# RJ45-1.net
KiCad netlist of a schematic drawn in Altium Designer
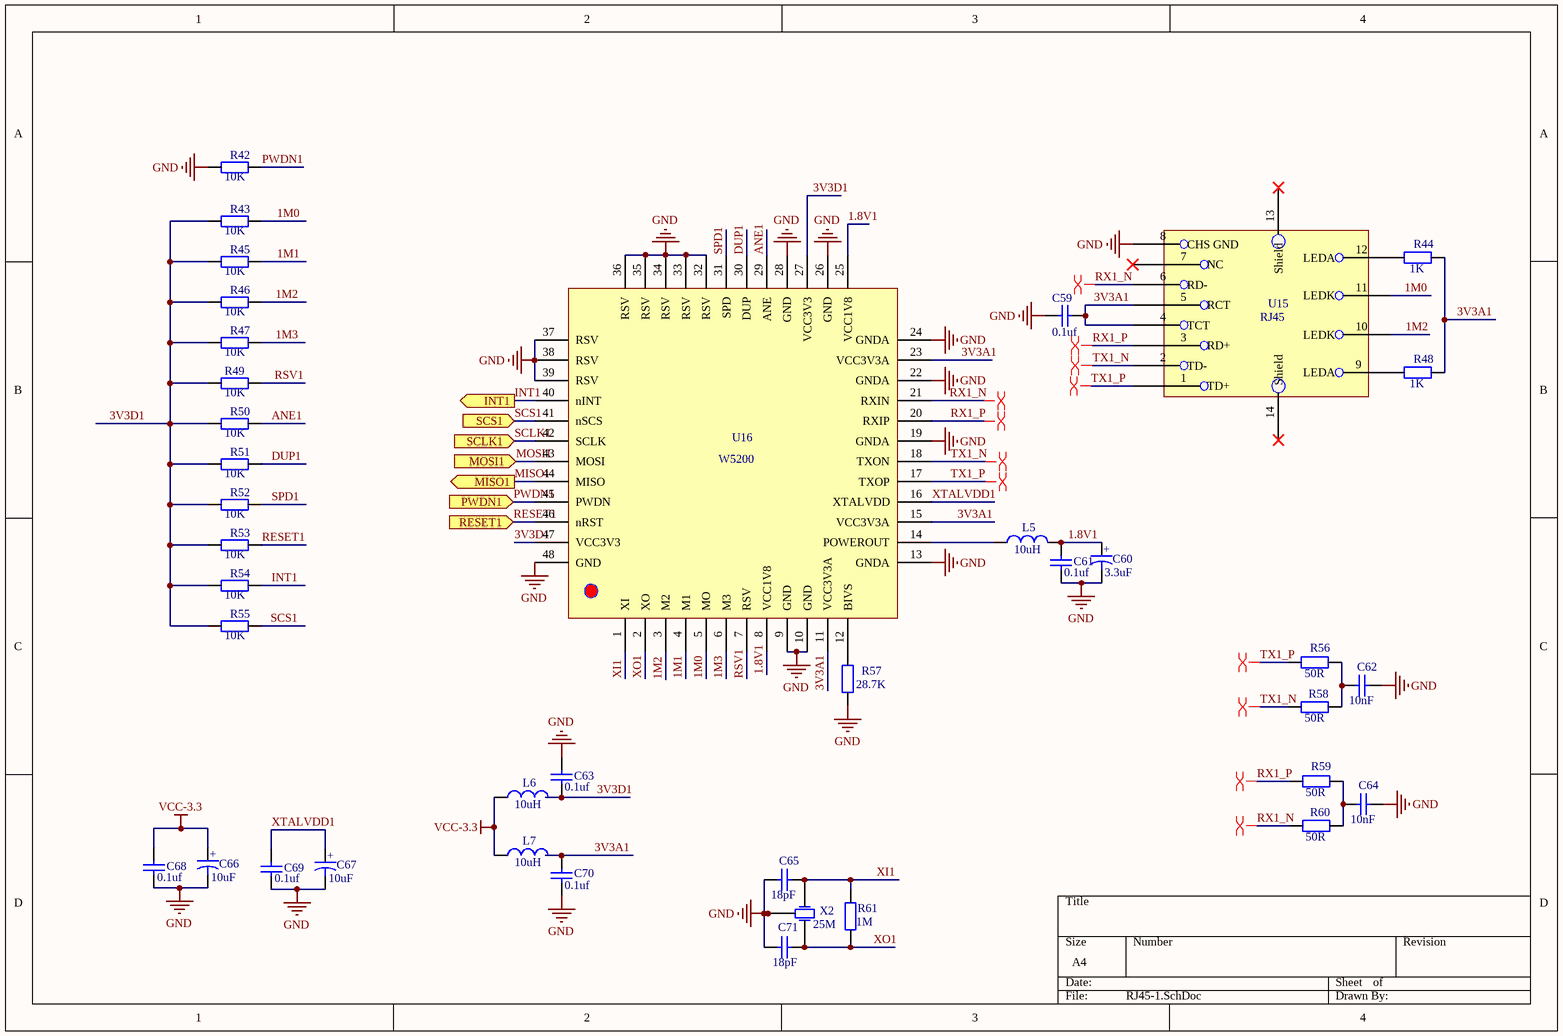
[diagram p0: RJ45-1.SchDoc]

(export (version "E")
  (design (tool "Eeschema 10.0.6"))
  (components
    (comp (ref "C59")
      (value "0.1uf")
      (footprint "0603")
      (fields (field (name "Comment") "Capacitor-0603"))
      (libsource (lib "原理图库") (part "Capacitor-0603"))
    )
    (comp (ref "C60")
      (value "3.3uF")
      (footprint "钽电容1206（A3216）")
      (fields (field (name "ALTIUM_UNNAMED_1") "+") (field (name "Comment") "电解电容"))
      (libsource (lib "原理图库") (part "电解电容"))
    )
    (comp (ref "C61")
      (value "0.1uf")
      (footprint "0603")
      (fields (field (name "Comment") "Capacitor-0603"))
      (libsource (lib "原理图库") (part "Capacitor-0603"))
    )
    (comp (ref "C62")
      (value "10nF")
      (footprint "0603")
      (fields (field (name "Comment") "Capacitor-0603"))
      (libsource (lib "原理图库") (part "Capacitor-0603"))
    )
    (comp (ref "C63")
      (value "0.1uf")
      (footprint "0603")
      (fields (field (name "Comment") "Capacitor-0603"))
      (libsource (lib "原理图库") (part "Capacitor-0603"))
    )
    (comp (ref "C64")
      (value "10nF")
      (footprint "0603")
      (fields (field (name "Comment") "Capacitor-0603"))
      (libsource (lib "原理图库") (part "Capacitor-0603"))
    )
    (comp (ref "C65")
      (value "18pF")
      (footprint "0603")
      (fields (field (name "Comment") "Capacitor-0603"))
      (libsource (lib "原理图库") (part "Capacitor-0603"))
    )
    (comp (ref "C66")
      (value "10uF")
      (footprint "钽电容1206（A3216）")
      (fields (field (name "ALTIUM_UNNAMED_1") "+") (field (name "Comment") "电解电容"))
      (libsource (lib "原理图库") (part "电解电容"))
    )
    (comp (ref "C67")
      (value "10uF")
      (footprint "钽电容1206（A3216）")
      (fields (field (name "ALTIUM_UNNAMED_1") "+") (field (name "Comment") "电解电容"))
      (libsource (lib "原理图库") (part "电解电容"))
    )
    (comp (ref "C68")
      (value "0.1uf")
      (footprint "0603")
      (fields (field (name "Comment") "Capacitor-0603"))
      (libsource (lib "原理图库") (part "Capacitor-0603"))
    )
    (comp (ref "C69")
      (value "0.1uf")
      (footprint "0603")
      (fields (field (name "Comment") "Capacitor-0603"))
      (libsource (lib "原理图库") (part "Capacitor-0603"))
    )
    (comp (ref "C70")
      (value "0.1uf")
      (footprint "0603")
      (fields (field (name "Comment") "Capacitor-0603"))
      (libsource (lib "原理图库") (part "Capacitor-0603"))
    )
    (comp (ref "C71")
      (value "18pF")
      (footprint "0603")
      (fields (field (name "Comment") "Capacitor-0603"))
      (libsource (lib "原理图库") (part "Capacitor-0603"))
    )
    (comp (ref "L5")
      (value "10uH")
      (footprint "0805")
      (fields (field (name "Comment") "Inductor"))
      (libsource (lib "原理图库") (part "Inductor"))
    )
    (comp (ref "L6")
      (value "10uH")
      (footprint "0805")
      (fields (field (name "Comment") "Inductor"))
      (libsource (lib "原理图库") (part "Inductor"))
    )
    (comp (ref "L7")
      (value "10uH")
      (footprint "0805")
      (fields (field (name "Comment") "Inductor"))
      (libsource (lib "原理图库") (part "Inductor"))
    )
    (comp (ref "R42")
      (value "10K")
      (footprint "0603")
      (fields (field (name "Comment") "Resistor-0603"))
      (libsource (lib "原理图库") (part "Resistor-0603"))
    )
    (comp (ref "R43")
      (value "10K")
      (footprint "0603")
      (fields (field (name "Comment") "Resistor-0603"))
      (libsource (lib "原理图库") (part "Resistor-0603"))
    )
    (comp (ref "R44")
      (value "1K")
      (footprint "0603")
      (fields (field (name "Comment") "Resistor-0603"))
      (libsource (lib "原理图库") (part "Resistor-0603"))
    )
    (comp (ref "R45")
      (value "10K")
      (footprint "0603")
      (fields (field (name "Comment") "Resistor-0603"))
      (libsource (lib "原理图库") (part "Resistor-0603"))
    )
    (comp (ref "R46")
      (value "10K")
      (footprint "0603")
      (fields (field (name "Comment") "Resistor-0603"))
      (libsource (lib "原理图库") (part "Resistor-0603"))
    )
    (comp (ref "R47")
      (value "10K")
      (footprint "0603")
      (fields (field (name "Comment") "Resistor-0603"))
      (libsource (lib "原理图库") (part "Resistor-0603"))
    )
    (comp (ref "R48")
      (value "1K")
      (footprint "0603")
      (fields (field (name "Comment") "Resistor-0603"))
      (libsource (lib "原理图库") (part "Resistor-0603"))
    )
    (comp (ref "R49")
      (value "10K")
      (footprint "0603")
      (fields (field (name "Comment") "Resistor-0603"))
      (libsource (lib "原理图库") (part "Resistor-0603"))
    )
    (comp (ref "R50")
      (value "10K")
      (footprint "0603")
      (fields (field (name "Comment") "Resistor-0603"))
      (libsource (lib "原理图库") (part "Resistor-0603"))
    )
    (comp (ref "R51")
      (value "10K")
      (footprint "0603")
      (fields (field (name "Comment") "Resistor-0603"))
      (libsource (lib "原理图库") (part "Resistor-0603"))
    )
    (comp (ref "R52")
      (value "10K")
      (footprint "0603")
      (fields (field (name "Comment") "Resistor-0603"))
      (libsource (lib "原理图库") (part "Resistor-0603"))
    )
    (comp (ref "R53")
      (value "10K")
      (footprint "0603")
      (fields (field (name "Comment") "Resistor-0603"))
      (libsource (lib "原理图库") (part "Resistor-0603"))
    )
    (comp (ref "R54")
      (value "10K")
      (footprint "0603")
      (fields (field (name "Comment") "Resistor-0603"))
      (libsource (lib "原理图库") (part "Resistor-0603"))
    )
    (comp (ref "R55")
      (value "10K")
      (footprint "0603")
      (fields (field (name "Comment") "Resistor-0603"))
      (libsource (lib "原理图库") (part "Resistor-0603"))
    )
    (comp (ref "R56")
      (value "50R")
      (footprint "0603")
      (fields (field (name "Comment") "Resistor-0603"))
      (libsource (lib "原理图库") (part "Resistor-0603"))
    )
    (comp (ref "R57")
      (value "28.7K")
      (footprint "0603")
      (fields (field (name "Comment") "Resistor-0603"))
      (libsource (lib "") (part "Resistor-0603_1"))
    )
    (comp (ref "R58")
      (value "50R")
      (footprint "0603")
      (fields (field (name "Comment") "Resistor-0603"))
      (libsource (lib "原理图库") (part "Resistor-0603"))
    )
    (comp (ref "R59")
      (value "50R")
      (footprint "0603")
      (fields (field (name "Comment") "Resistor-0603"))
      (libsource (lib "原理图库") (part "Resistor-0603"))
    )
    (comp (ref "R60")
      (value "50R")
      (footprint "0603")
      (fields (field (name "Comment") "Resistor-0603"))
      (libsource (lib "原理图库") (part "Resistor-0603"))
    )
    (comp (ref "R61")
      (value "1M")
      (footprint "0603")
      (fields (field (name "Comment") "Resistor-0603"))
      (libsource (lib "") (part "Resistor-0603_2"))
    )
    (comp (ref "U15")
      (value "RJ45")
      (footprint "RJ45")
      (fields (field (name "NAME") "RJ45"))
      (libsource (lib "原理图库") (part "RJ45"))
    )
    (comp (ref "U16")
      (value "W5200-Chip")
      (footprint "W5200-Chip")
      (fields (field (name "NAME") "W5200"))
      (libsource (lib "原理图库") (part "W5200-Chip"))
    )
    (comp (ref "X2")
      (value "25M")
      (footprint "3225无源晶振")
      (fields (field (name "Comment") "3225无源晶振"))
      (libsource (lib "原理图库") (part "3225无源晶振"))
    )
  )
  (nets
    (net (code "1") (name "/1.8V1") (class "Default")
      (node (ref "C60") (pin "2") (pinfunction "2_2") (pintype "passive"))
      (node (ref "C61") (pin "2") (pinfunction "2_2") (pintype "passive"))
      (node (ref "L5") (pin "2") (pinfunction "2_2") (pintype "passive"))
      (node (ref "U16") (pin "25") (pinfunction "VCC1V8_25") (pintype "passive"))
      (node (ref "U16") (pin "8") (pinfunction "VCC1V8_8") (pintype "passive"))
    )
    (net (code "2") (name "/1M0") (class "Default")
      (node (ref "R43") (pin "2") (pinfunction "2_2") (pintype "passive"))
      (node (ref "U15") (pin "11") (pinfunction "LEDK_11") (pintype "passive"))
      (node (ref "U16") (pin "5") (pinfunction "MO_5") (pintype "passive"))
    )
    (net (code "3") (name "/1M1") (class "Default")
      (node (ref "R45") (pin "2") (pinfunction "2_2") (pintype "passive"))
      (node (ref "U16") (pin "4") (pinfunction "M1_4") (pintype "passive"))
    )
    (net (code "4") (name "/1M2") (class "Default")
      (node (ref "R46") (pin "2") (pinfunction "2_2") (pintype "passive"))
      (node (ref "U15") (pin "10") (pinfunction "LEDK_10") (pintype "passive"))
      (node (ref "U16") (pin "3") (pinfunction "M2_3") (pintype "passive"))
    )
    (net (code "5") (name "/1M3") (class "Default")
      (node (ref "R47") (pin "2") (pinfunction "2_2") (pintype "passive"))
      (node (ref "U16") (pin "6") (pinfunction "M3_6") (pintype "passive"))
    )
    (net (code "6") (name "/3V3A1") (class "Default")
      (node (ref "C59") (pin "1") (pinfunction "1_1") (pintype "passive"))
      (node (ref "C70") (pin "1") (pinfunction "1_1") (pintype "passive"))
      (node (ref "L7") (pin "2") (pinfunction "2_2") (pintype "passive"))
      (node (ref "R44") (pin "2") (pinfunction "2_2") (pintype "passive"))
      (node (ref "R48") (pin "2") (pinfunction "2_2") (pintype "passive"))
      (node (ref "U15") (pin "4") (pinfunction "TCT_4") (pintype "passive"))
      (node (ref "U15") (pin "5") (pinfunction "RCT_5") (pintype "passive"))
      (node (ref "U16") (pin "11") (pinfunction "VCC3V3A_11") (pintype "passive"))
      (node (ref "U16") (pin "15") (pinfunction "VCC3V3A_15") (pintype "passive"))
      (node (ref "U16") (pin "23") (pinfunction "VCC3V3A_23") (pintype "passive"))
    )
    (net (code "7") (name "/3V3D1") (class "Default")
      (node (ref "C63") (pin "1") (pinfunction "1_1") (pintype "passive"))
      (node (ref "L6") (pin "2") (pinfunction "2_2") (pintype "passive"))
      (node (ref "R43") (pin "1") (pinfunction "1_1") (pintype "passive"))
      (node (ref "R45") (pin "1") (pinfunction "1_1") (pintype "passive"))
      (node (ref "R46") (pin "1") (pinfunction "1_1") (pintype "passive"))
      (node (ref "R47") (pin "1") (pinfunction "1_1") (pintype "passive"))
      (node (ref "R49") (pin "1") (pinfunction "1_1") (pintype "passive"))
      (node (ref "R50") (pin "1") (pinfunction "1_1") (pintype "passive"))
      (node (ref "R51") (pin "1") (pinfunction "1_1") (pintype "passive"))
      (node (ref "R52") (pin "1") (pinfunction "1_1") (pintype "passive"))
      (node (ref "R53") (pin "1") (pinfunction "1_1") (pintype "passive"))
      (node (ref "R54") (pin "1") (pinfunction "1_1") (pintype "passive"))
      (node (ref "R55") (pin "1") (pinfunction "1_1") (pintype "passive"))
      (node (ref "U16") (pin "27") (pinfunction "VCC3V3_27") (pintype "passive"))
      (node (ref "U16") (pin "47") (pinfunction "VCC3V3_47") (pintype "passive"))
    )
    (net (code "8") (name "/ANE1") (class "Default")
      (node (ref "R50") (pin "2") (pinfunction "2_2") (pintype "passive"))
      (node (ref "U16") (pin "29") (pinfunction "ANE_29") (pintype "passive"))
    )
    (net (code "9") (name "/DUP1") (class "Default")
      (node (ref "R51") (pin "2") (pinfunction "2_2") (pintype "passive"))
      (node (ref "U16") (pin "30") (pinfunction "DUP_30") (pintype "passive"))
    )
    (net (code "10") (name "/INT1") (class "Default")
      (node (ref "R54") (pin "2") (pinfunction "2_2") (pintype "passive"))
      (node (ref "U16") (pin "40") (pinfunction "nINT_40") (pintype "passive"))
    )
    (net (code "11") (name "/MISO1") (class "Default")
      (node (ref "U16") (pin "44") (pinfunction "MISO_44") (pintype "passive"))
    )
    (net (code "12") (name "/MOSI1") (class "Default")
      (node (ref "U16") (pin "43") (pinfunction "MOSI_43") (pintype "passive"))
    )
    (net (code "13") (name "/PWDN1") (class "Default")
      (node (ref "R42") (pin "2") (pinfunction "2_2") (pintype "passive"))
      (node (ref "U16") (pin "45") (pinfunction "PWDN_45") (pintype "passive"))
    )
    (net (code "14") (name "/RESET1") (class "Default")
      (node (ref "R53") (pin "2") (pinfunction "2_2") (pintype "passive"))
      (node (ref "U16") (pin "46") (pinfunction "nRST_46") (pintype "passive"))
    )
    (net (code "15") (name "/RSV1") (class "Default")
      (node (ref "R49") (pin "2") (pinfunction "2_2") (pintype "passive"))
      (node (ref "U16") (pin "7") (pinfunction "RSV_7") (pintype "passive"))
    )
    (net (code "16") (name "/RX1_N") (class "Default")
      (node (ref "R60") (pin "1") (pinfunction "1_1") (pintype "passive"))
      (node (ref "U15") (pin "6") (pinfunction "RD-_6") (pintype "passive"))
      (node (ref "U16") (pin "21") (pinfunction "RXIN_21") (pintype "passive"))
    )
    (net (code "17") (name "/RX1_P") (class "Default")
      (node (ref "R59") (pin "1") (pinfunction "1_1") (pintype "passive"))
      (node (ref "U15") (pin "3") (pinfunction "RD+_3") (pintype "passive"))
      (node (ref "U16") (pin "20") (pinfunction "RXIP_20") (pintype "passive"))
    )
    (net (code "18") (name "/SCLK1") (class "Default")
      (node (ref "U16") (pin "42") (pinfunction "SCLK_42") (pintype "passive"))
    )
    (net (code "19") (name "/SCS1") (class "Default")
      (node (ref "R55") (pin "2") (pinfunction "2_2") (pintype "passive"))
      (node (ref "U16") (pin "41") (pinfunction "nSCS_41") (pintype "passive"))
    )
    (net (code "20") (name "/SPD1") (class "Default")
      (node (ref "R52") (pin "2") (pinfunction "2_2") (pintype "passive"))
      (node (ref "U16") (pin "31") (pinfunction "SPD_31") (pintype "passive"))
    )
    (net (code "21") (name "/TX1_N") (class "Default")
      (node (ref "R58") (pin "1") (pinfunction "1_1") (pintype "passive"))
      (node (ref "U15") (pin "2") (pinfunction "TD-_2") (pintype "passive"))
      (node (ref "U16") (pin "18") (pinfunction "TXON_18") (pintype "passive"))
    )
    (net (code "22") (name "/TX1_P") (class "Default")
      (node (ref "R56") (pin "1") (pinfunction "1_1") (pintype "passive"))
      (node (ref "U15") (pin "1") (pinfunction "TD+_1") (pintype "passive"))
      (node (ref "U16") (pin "17") (pinfunction "TXOP_17") (pintype "passive"))
    )
    (net (code "23") (name "/XI1") (class "Default")
      (node (ref "C65") (pin "2") (pinfunction "2_2") (pintype "passive"))
      (node (ref "R61") (pin "1") (pinfunction "1_1") (pintype "passive"))
      (node (ref "U16") (pin "1") (pinfunction "XI_1") (pintype "passive"))
      (node (ref "X2") (pin "1") (pinfunction "OSC1_1") (pintype "passive"))
    )
    (net (code "24") (name "/XO1") (class "Default")
      (node (ref "C71") (pin "2") (pinfunction "2_2") (pintype "passive"))
      (node (ref "R61") (pin "2") (pinfunction "2_2") (pintype "passive"))
      (node (ref "U16") (pin "2") (pinfunction "XO_2") (pintype "passive"))
      (node (ref "X2") (pin "3") (pinfunction "OSC2_3") (pintype "passive"))
    )
    (net (code "25") (name "/XTALVDD1") (class "Default")
      (node (ref "C67") (pin "2") (pinfunction "2_2") (pintype "passive"))
      (node (ref "C69") (pin "2") (pinfunction "2_2") (pintype "passive"))
      (node (ref "U16") (pin "16") (pinfunction "XTALVDD_16") (pintype "passive"))
    )
    (net (code "26") (name "GND") (class "Default")
      (node (ref "C59") (pin "2") (pinfunction "2_2") (pintype "passive"))
      (node (ref "C60") (pin "1") (pinfunction "1_1") (pintype "passive"))
      (node (ref "C61") (pin "1") (pinfunction "1_1") (pintype "passive"))
      (node (ref "C62") (pin "2") (pinfunction "2_2") (pintype "passive"))
      (node (ref "C63") (pin "2") (pinfunction "2_2") (pintype "passive"))
      (node (ref "C64") (pin "2") (pinfunction "2_2") (pintype "passive"))
      (node (ref "C65") (pin "1") (pinfunction "1_1") (pintype "passive"))
      (node (ref "C66") (pin "1") (pinfunction "1_1") (pintype "passive"))
      (node (ref "C67") (pin "1") (pinfunction "1_1") (pintype "passive"))
      (node (ref "C68") (pin "1") (pinfunction "1_1") (pintype "passive"))
      (node (ref "C69") (pin "1") (pinfunction "1_1") (pintype "passive"))
      (node (ref "C70") (pin "2") (pinfunction "2_2") (pintype "passive"))
      (node (ref "C71") (pin "1") (pinfunction "1_1") (pintype "passive"))
      (node (ref "R42") (pin "1") (pinfunction "1_1") (pintype "passive"))
      (node (ref "R57") (pin "1") (pinfunction "1_1") (pintype "passive"))
      (node (ref "U15") (pin "8") (pinfunction "CHS_GND_8") (pintype "passive"))
      (node (ref "U16") (pin "10") (pinfunction "GND_10") (pintype "passive"))
      (node (ref "U16") (pin "13") (pinfunction "GNDA_13") (pintype "passive"))
      (node (ref "U16") (pin "19") (pinfunction "GNDA_19") (pintype "passive"))
      (node (ref "U16") (pin "22") (pinfunction "GNDA_22") (pintype "passive"))
      (node (ref "U16") (pin "24") (pinfunction "GNDA_24") (pintype "passive"))
      (node (ref "U16") (pin "26") (pinfunction "GND_26") (pintype "passive"))
      (node (ref "U16") (pin "28") (pinfunction "GND_28") (pintype "passive"))
      (node (ref "U16") (pin "32") (pinfunction "RSV_32") (pintype "passive"))
      (node (ref "U16") (pin "33") (pinfunction "RSV_33") (pintype "passive"))
      (node (ref "U16") (pin "34") (pinfunction "RSV_34") (pintype "passive"))
      (node (ref "U16") (pin "35") (pinfunction "RSV_35") (pintype "passive"))
      (node (ref "U16") (pin "36") (pinfunction "RSV_36") (pintype "passive"))
      (node (ref "U16") (pin "37") (pinfunction "RSV_37") (pintype "passive"))
      (node (ref "U16") (pin "38") (pinfunction "RSV_38") (pintype "passive"))
      (node (ref "U16") (pin "39") (pinfunction "RSV_39") (pintype "passive"))
      (node (ref "U16") (pin "48") (pinfunction "GND_48") (pintype "passive"))
      (node (ref "U16") (pin "9") (pinfunction "GND_9") (pintype "passive"))
      (node (ref "X2") (pin "2") (pinfunction "GND_2") (pintype "passive"))
      (node (ref "X2") (pin "4") (pinfunction "GND_4") (pintype "passive"))
    )
    (net (code "27") (name "Net-(C62-Pad1)") (class "Default")
      (node (ref "C62") (pin "1") (pinfunction "1_1") (pintype "passive"))
      (node (ref "R56") (pin "2") (pinfunction "2_2") (pintype "passive"))
      (node (ref "R58") (pin "2") (pinfunction "2_2") (pintype "passive"))
    )
    (net (code "28") (name "Net-(C64-Pad1)") (class "Default")
      (node (ref "C64") (pin "1") (pinfunction "1_1") (pintype "passive"))
      (node (ref "R59") (pin "2") (pinfunction "2_2") (pintype "passive"))
      (node (ref "R60") (pin "2") (pinfunction "2_2") (pintype "passive"))
    )
    (net (code "29") (name "Net-(R44-Pad1)") (class "Default")
      (node (ref "R44") (pin "1") (pinfunction "1_1") (pintype "passive"))
      (node (ref "U15") (pin "12") (pinfunction "LEDA_12") (pintype "passive"))
    )
    (net (code "30") (name "Net-(R48-Pad1)") (class "Default")
      (node (ref "R48") (pin "1") (pinfunction "1_1") (pintype "passive"))
      (node (ref "U15") (pin "9") (pinfunction "LEDA_9") (pintype "passive"))
    )
    (net (code "31") (name "Net-(U16-BIVS)") (class "Default")
      (node (ref "R57") (pin "2") (pinfunction "2_2") (pintype "passive"))
      (node (ref "U16") (pin "12") (pinfunction "BIVS_12") (pintype "passive"))
    )
    (net (code "32") (name "Net-(U16-POWEROUT)") (class "Default")
      (node (ref "L5") (pin "1") (pinfunction "1_1") (pintype "passive"))
      (node (ref "U16") (pin "14") (pinfunction "POWEROUT_14") (pintype "passive"))
    )
    (net (code "33") (name "VCC-3.3") (class "Default")
      (node (ref "C66") (pin "2") (pinfunction "2_2") (pintype "passive"))
      (node (ref "C68") (pin "2") (pinfunction "2_2") (pintype "passive"))
      (node (ref "L6") (pin "1") (pinfunction "1_1") (pintype "passive"))
      (node (ref "L7") (pin "1") (pinfunction "1_1") (pintype "passive"))
    )
    (net (code "34") (name "unconnected-(U15-NC-Pad7)") (class "Default")
      (node (ref "U15") (pin "7") (pinfunction "NC_7") (pintype "passive+no_connect"))
    )
    (net (code "35") (name "unconnected-(U15-Shield-Pad13)") (class "Default")
      (node (ref "U15") (pin "13") (pinfunction "Shield_13") (pintype "passive+no_connect"))
    )
    (net (code "36") (name "unconnected-(U15-Shield-Pad14)") (class "Default")
      (node (ref "U15") (pin "14") (pinfunction "Shield_14") (pintype "passive+no_connect"))
    )
  )
)
